# 02-WWVB_Path.net
KiCad netlist of a schematic drawn in Altium Designer
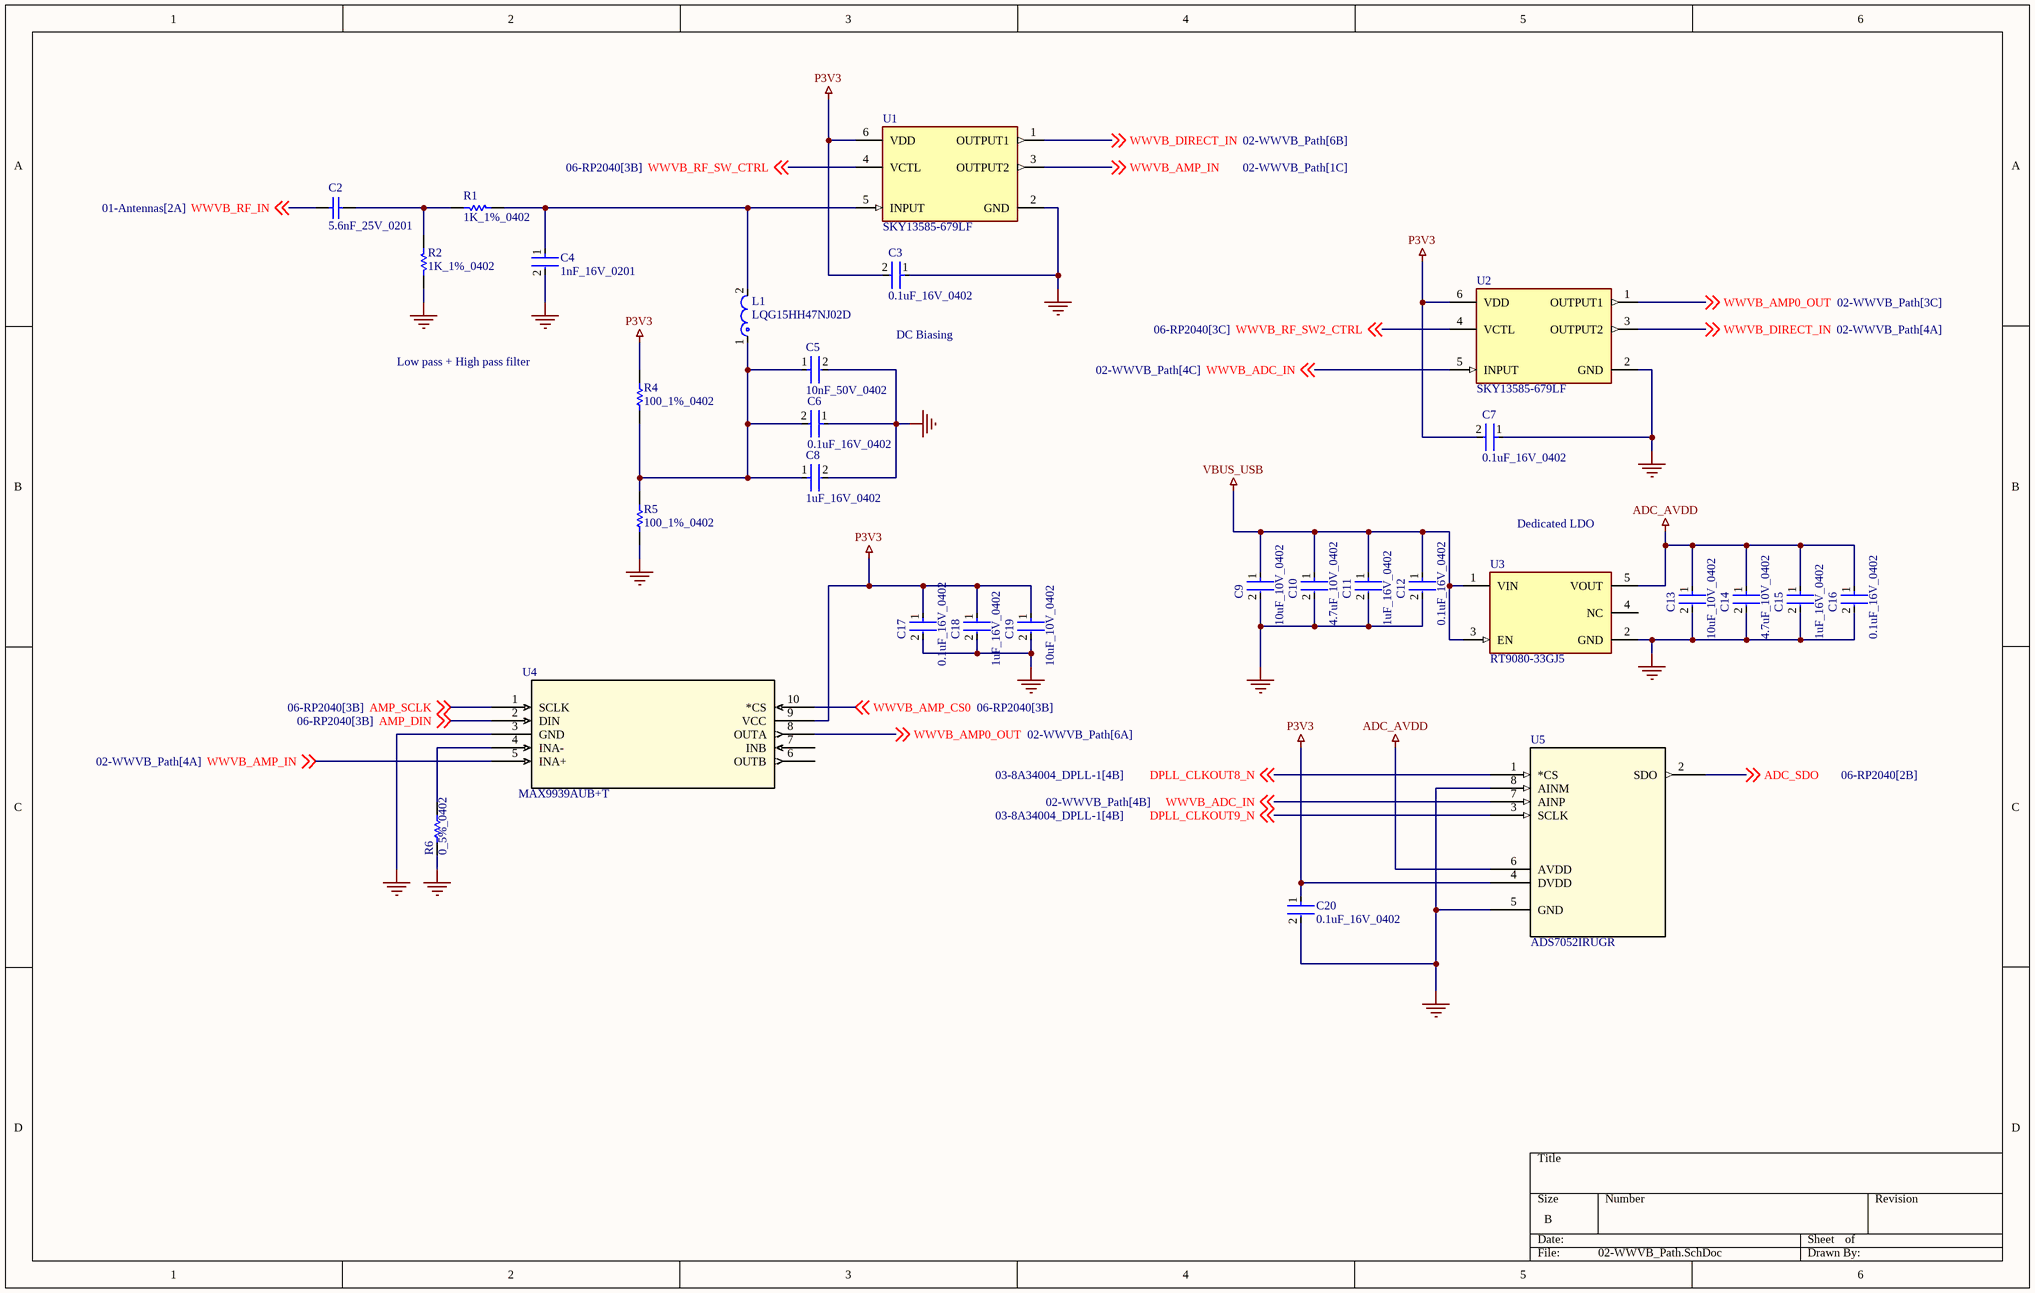
[diagram p0: 02-WWVB_Path.SchDoc]

(export (version "E")
  (design (tool "Eeschema 10.0.6"))
  (components
    (comp (ref "C2")
      (value "5.6nF_25V_0201")
      (footprint "CAPC0603X33X15ML03T05")
      (fields (field (name "PART NUMBER") "MC000322") (field (name "MANUFACTURER") "Multicomp"))
      (libsource (lib "Altium Content Vault") (part "CAP"))
    )
    (comp (ref "C3")
      (value "0.1uF_16V_0402")
      (footprint "FP-C0402-BB-MFG")
      (description "CAP CER 0.1UF 16V 5% X7R 0402")
      (fields
        (field (name "MANUFACTURER") "Kemet")
        (field (name "MANUFACTURER PART NUMBER") "C0402C104J4RACTU")
      )
      (libsource (lib "Altium Content Vault") (part "b4654b650e69147ec39a6b967a45e02"))
    )
    (comp (ref "C4")
      (value "1nF_16V_0201")
      (footprint "FP-0201-L_0_6_0_09-W_0_3-MFG")
      (description "General Purpose Ceramic Capacitor, 0201, 1nF, 10%, X7R, 15%, 16V")
      (fields (field (name "VOLTAGE") "16V") (field (name "TOLERANCE") "10%"))
      (libsource (lib "Altium Content Vault") (part "b4654b650e69147ec39a6b967a45e02"))
    )
    (comp (ref "C5")
      (value "10nF_50V_0402")
      (footprint "FP-CL165-IPC_C")
      (description "Cap Ceramic 10nF 50V X7R ±10% SMD 0402 +125°C Paper T/R")
      (fields (field (name "VOLTAGE") "50V") (field (name "TOLERANCE") "10%"))
      (libsource (lib "Altium Content Vault") (part "b4654b650e69147ec39a6b967a45e02"))
    )
    (comp (ref "C6")
      (value "0.1uF_16V_0402")
      (footprint "FP-C0402-BB-MFG")
      (description "CAP CER 0.1UF 16V 5% X7R 0402")
      (fields
        (field (name "MANUFACTURER") "Kemet")
        (field (name "MANUFACTURER PART NUMBER") "C0402C104J4RACTU")
      )
      (libsource (lib "Altium Content Vault") (part "b4654b650e69147ec39a6b967a45e02"))
    )
    (comp (ref "C7")
      (value "0.1uF_16V_0402")
      (footprint "FP-C0402-BB-MFG")
      (description "CAP CER 0.1UF 16V 5% X7R 0402")
      (fields
        (field (name "MANUFACTURER") "Kemet")
        (field (name "MANUFACTURER PART NUMBER") "C0402C104J4RACTU")
      )
      (libsource (lib "Altium Content Vault") (part "b4654b650e69147ec39a6b967a45e02"))
    )
    (comp (ref "C8")
      (value "1uF_16V_0402")
      (footprint "FP-0402-L_1_0_0_05-W_0_5-IPC_A")
      (description "None")
      (fields (field (name "TOLERANCE") "10%"))
      (libsource (lib "Altium Content Vault") (part "b4654b650e69147ec39a6b967a45e02"))
    )
    (comp (ref "C9")
      (value "10uF_10V_0402")
      (footprint "FP-CL05A106MP5NUNC-MFG")
      (description "CAP CER 10UF 10V X5R 0402")
      (fields
        (field (name "OCTOPART") "https://octopart.com/cl05a106mp5nunc-samsung-22457395")
        (field (name "TOLERANCE") "20%")
      )
      (libsource (lib "Altium Content Vault") (part "b4654b650e69147ec39a6b967a45e02"))
    )
    (comp (ref "C10")
      (value "4.7uF_10V_0402")
      (footprint "FP-C1005-050-0_15-MFG")
      (description "CAP CER 4.7UF 10V X5R 0402")
      (fields (field (name "TOLERANCE") "10%"))
      (libsource (lib "Altium Content Vault") (part "b4654b650e69147ec39a6b967a45e02"))
    )
    (comp (ref "C11")
      (value "1uF_16V_0402")
      (footprint "FP-0402-L_1_0_0_05-W_0_5-IPC_A")
      (description "None")
      (fields (field (name "TOLERANCE") "10%"))
      (libsource (lib "Altium Content Vault") (part "b4654b650e69147ec39a6b967a45e02"))
    )
    (comp (ref "C12")
      (value "0.1uF_16V_0402")
      (footprint "FP-C0402-BB-MFG")
      (description "CAP CER 0.1UF 16V 5% X7R 0402")
      (fields
        (field (name "MANUFACTURER") "Kemet")
        (field (name "MANUFACTURER PART NUMBER") "C0402C104J4RACTU")
      )
      (libsource (lib "Altium Content Vault") (part "b4654b650e69147ec39a6b967a45e02"))
    )
    (comp (ref "C13")
      (value "10uF_10V_0402")
      (footprint "FP-CL05A106MP5NUNC-MFG")
      (description "CAP CER 10UF 10V X5R 0402")
      (fields
        (field (name "OCTOPART") "https://octopart.com/cl05a106mp5nunc-samsung-22457395")
        (field (name "TOLERANCE") "20%")
      )
      (libsource (lib "Altium Content Vault") (part "b4654b650e69147ec39a6b967a45e02"))
    )
    (comp (ref "C14")
      (value "4.7uF_10V_0402")
      (footprint "FP-C1005-050-0_15-MFG")
      (description "CAP CER 4.7UF 10V X5R 0402")
      (fields (field (name "TOLERANCE") "10%"))
      (libsource (lib "Altium Content Vault") (part "b4654b650e69147ec39a6b967a45e02"))
    )
    (comp (ref "C15")
      (value "1uF_16V_0402")
      (footprint "FP-0402-L_1_0_0_05-W_0_5-IPC_A")
      (description "None")
      (fields (field (name "TOLERANCE") "10%"))
      (libsource (lib "Altium Content Vault") (part "b4654b650e69147ec39a6b967a45e02"))
    )
    (comp (ref "C16")
      (value "0.1uF_16V_0402")
      (footprint "FP-C0402-BB-MFG")
      (description "CAP CER 0.1UF 16V 5% X7R 0402")
      (fields
        (field (name "MANUFACTURER") "Kemet")
        (field (name "MANUFACTURER PART NUMBER") "C0402C104J4RACTU")
      )
      (libsource (lib "Altium Content Vault") (part "b4654b650e69147ec39a6b967a45e02"))
    )
    (comp (ref "C17")
      (value "0.1uF_16V_0402")
      (footprint "FP-C0402-BB-MFG")
      (description "CAP CER 0.1UF 16V 5% X7R 0402")
      (fields
        (field (name "MANUFACTURER") "Kemet")
        (field (name "MANUFACTURER PART NUMBER") "C0402C104J4RACTU")
      )
      (libsource (lib "Altium Content Vault") (part "b4654b650e69147ec39a6b967a45e02"))
    )
    (comp (ref "C18")
      (value "1uF_16V_0402")
      (footprint "FP-0402-L_1_0_0_05-W_0_5-IPC_A")
      (description "None")
      (fields (field (name "TOLERANCE") "10%"))
      (libsource (lib "Altium Content Vault") (part "b4654b650e69147ec39a6b967a45e02"))
    )
    (comp (ref "C19")
      (value "10uF_10V_0402")
      (footprint "FP-CL05A106MP5NUNC-MFG")
      (description "CAP CER 10UF 10V X5R 0402")
      (fields
        (field (name "OCTOPART") "https://octopart.com/cl05a106mp5nunc-samsung-22457395")
        (field (name "TOLERANCE") "20%")
      )
      (libsource (lib "Altium Content Vault") (part "b4654b650e69147ec39a6b967a45e02"))
    )
    (comp (ref "C20")
      (value "0.1uF_16V_0402")
      (footprint "FP-C0402-BB-MFG")
      (description "CAP CER 0.1UF 16V 5% X7R 0402")
      (fields
        (field (name "MANUFACTURER") "Kemet")
        (field (name "MANUFACTURER PART NUMBER") "C0402C104J4RACTU")
      )
      (libsource (lib "Altium Content Vault") (part "b4654b650e69147ec39a6b967a45e02"))
    )
    (comp (ref "L1")
      (value "LQG15HH47NJ02D")
      (footprint "FP-LQG15HH_02-IPC_C")
      (description "Multilayer type Inductor for Automotive 47nH ±5% 0.72Ω 300mA 0402")
      (fields (field (name "TOLERANCE") "5%"))
      (libsource (lib "Altium Content Vault") (part "4cc4b267dca4c8e51f7102f422741d8"))
    )
    (comp (ref "R1")
      (value "1K_1%_0402")
      (footprint "RESC1005X40X25NL05T05")
      (fields (field (name "MANUFACTURER") "Vishay Dale") (field (name "PART NUMBER") "CRCW04021K00FKTD"))
      (libsource (lib "Altium Content Vault") (part "RES"))
    )
    (comp (ref "R2")
      (value "1K_1%_0402")
      (footprint "RESC1005X40X25NL05T05")
      (fields (field (name "MANUFACTURER") "Vishay Dale") (field (name "PART NUMBER") "CRCW04021K00FKTD"))
      (libsource (lib "Altium Content Vault") (part "RES"))
    )
    (comp (ref "R4")
      (value "100_1%_0402")
      (footprint "RESC1005X40X25ML05T10")
      (fields (field (name "PART NUMBER") "ERJ-U02F1000X") (field (name "MANUFACTURER") "Panasonic"))
      (libsource (lib "Altium Content Vault") (part "RES"))
    )
    (comp (ref "R5")
      (value "100_1%_0402")
      (footprint "RESC1005X40X25ML05T10")
      (fields (field (name "PART NUMBER") "ERJ-U02F1000X") (field (name "MANUFACTURER") "Panasonic"))
      (libsource (lib "Altium Content Vault") (part "RES"))
    )
    (comp (ref "R6")
      (value "0_5%_0402")
      (footprint "RESC1005X40X25NL05T10")
      (fields (field (name "MANUFACTURER") "Panasonic") (field (name "PART NUMBER") "ERJ-U020R00X"))
      (libsource (lib "Altium Content Vault") (part "RES"))
    )
    (comp (ref "U1")
      (value "SKY13585-679LF")
      (footprint "FP-SKY13585-679LF-MFG")
      (description "IC RF SWITCH SPDT 6GHZ 6MLPD")
      (libsource (lib "Altium Content Vault") (part "e67e48af39ab44f3294fce00d3e4f12"))
    )
    (comp (ref "U2")
      (value "SKY13585-679LF")
      (footprint "FP-SKY13585-679LF-MFG")
      (description "IC RF SWITCH SPDT 6GHZ 6MLPD")
      (libsource (lib "Altium Content Vault") (part "e67e48af39ab44f3294fce00d3e4f12"))
    )
    (comp (ref "U3")
      (value "RT9080-33GJ5")
      (footprint "FP-RT9080-33GJ5-IPC_C")
      (description "IC REG LIN 3.3V 600MA TSOT23-5")
      (libsource (lib "Altium Content Vault") (part "f644620f29190e8f0733f9129712cb2"))
    )
    (comp (ref "U4")
      (value "MAX9939AUB+T")
      (footprint "21-0061L_MXM")
      (description "No Description Available")
      (fields (field (name "COPYRIGHT") "Copyright (C) 2023 Ultra Librarian. All rights reserved."))
      (libsource (lib "MAX9939AUB&plus_T") (part "MAX9939AUB+T"))
    )
    (comp (ref "U5")
      (value "ADS7052IRUGR")
      (footprint "RUG8_TEX")
      (description "No Description Available")
      (libsource (lib "ADS7052IRUGR") (part "ADS7052IRUGR"))
    )
  )
  (nets
    (net (code "1") (name "ADC_AVDD") (class "Default")
      (node (ref "C13") (pin "1") (pinfunction "1_1") (pintype "passive"))
      (node (ref "C14") (pin "1") (pinfunction "1_1") (pintype "passive"))
      (node (ref "C15") (pin "1") (pinfunction "1_1") (pintype "passive"))
      (node (ref "C16") (pin "1") (pinfunction "1_1") (pintype "passive"))
      (node (ref "U3") (pin "5") (pinfunction "VOUT_5") (pintype "passive"))
      (node (ref "U5") (pin "6") (pinfunction "AVDD_6") (pintype "power_in"))
    )
    (net (code "2") (name "ADC_SDO") (class "Default")
      (node (ref "U5") (pin "2") (pinfunction "SDO_2") (pintype "output"))
    )
    (net (code "3") (name "AMP_DIN") (class "Default")
      (node (ref "U4") (pin "2") (pinfunction "DIN_2") (pintype "input"))
    )
    (net (code "4") (name "AMP_SCLK") (class "Default")
      (node (ref "U4") (pin "1") (pinfunction "SCLK_1") (pintype "input"))
    )
    (net (code "5") (name "DPLL_CLKOUT8_N") (class "Default")
      (node (ref "U5") (pin "1") (pinfunction "*CS_1") (pintype "input"))
    )
    (net (code "6") (name "DPLL_CLKOUT9_N") (class "Default")
      (node (ref "U5") (pin "3") (pinfunction "SCLK_3") (pintype "input"))
    )
    (net (code "7") (name "GND") (class "Default")
      (node (ref "C10") (pin "2") (pinfunction "2_2") (pintype "passive"))
      (node (ref "C11") (pin "2") (pinfunction "2_2") (pintype "passive"))
      (node (ref "C12") (pin "2") (pinfunction "2_2") (pintype "passive"))
      (node (ref "C13") (pin "2") (pinfunction "2_2") (pintype "passive"))
      (node (ref "C14") (pin "2") (pinfunction "2_2") (pintype "passive"))
      (node (ref "C15") (pin "2") (pinfunction "2_2") (pintype "passive"))
      (node (ref "C16") (pin "2") (pinfunction "2_2") (pintype "passive"))
      (node (ref "C17") (pin "2") (pinfunction "2_2") (pintype "passive"))
      (node (ref "C18") (pin "2") (pinfunction "2_2") (pintype "passive"))
      (node (ref "C19") (pin "2") (pinfunction "2_2") (pintype "passive"))
      (node (ref "C20") (pin "2") (pinfunction "2_2") (pintype "passive"))
      (node (ref "C3") (pin "1") (pinfunction "1_1") (pintype "passive"))
      (node (ref "C4") (pin "2") (pinfunction "2_2") (pintype "passive"))
      (node (ref "C5") (pin "2") (pinfunction "2_2") (pintype "passive"))
      (node (ref "C6") (pin "1") (pinfunction "1_1") (pintype "passive"))
      (node (ref "C7") (pin "1") (pinfunction "1_1") (pintype "passive"))
      (node (ref "C8") (pin "2") (pinfunction "2_2") (pintype "passive"))
      (node (ref "C9") (pin "2") (pinfunction "2_2") (pintype "passive"))
      (node (ref "R2") (pin "1") (pinfunction "1_1") (pintype "passive"))
      (node (ref "R5") (pin "1") (pinfunction "1_1") (pintype "passive"))
      (node (ref "R6") (pin "1") (pinfunction "1_1") (pintype "passive"))
      (node (ref "U1") (pin "2") (pinfunction "GND_2") (pintype "power_in"))
      (node (ref "U2") (pin "2") (pinfunction "GND_2") (pintype "power_in"))
      (node (ref "U3") (pin "2") (pinfunction "GND_2") (pintype "power_in"))
      (node (ref "U4") (pin "3") (pinfunction "GND_3") (pintype "power_in"))
      (node (ref "U5") (pin "5") (pinfunction "GND_5") (pintype "power_in"))
      (node (ref "U5") (pin "8") (pinfunction "AINM_8") (pintype "input"))
    )
    (net (code "8") (name "Net-(C2-Pad2)") (class "Default")
      (node (ref "C2") (pin "2") (pinfunction "2_2") (pintype "passive"))
      (node (ref "R1") (pin "2") (pinfunction "2_2") (pintype "passive"))
      (node (ref "R2") (pin "2") (pinfunction "2_2") (pintype "passive"))
    )
    (net (code "9") (name "Net-(C5-Pad1)") (class "Default")
      (node (ref "C5") (pin "1") (pinfunction "1_1") (pintype "passive"))
      (node (ref "C6") (pin "2") (pinfunction "2_2") (pintype "passive"))
      (node (ref "C8") (pin "1") (pinfunction "1_1") (pintype "passive"))
      (node (ref "L1") (pin "1") (pinfunction "1_1") (pintype "passive"))
      (node (ref "R4") (pin "1") (pinfunction "1_1") (pintype "passive"))
      (node (ref "R5") (pin "2") (pinfunction "2_2") (pintype "passive"))
    )
    (net (code "10") (name "Net-(U1-INPUT)") (class "Default")
      (node (ref "C4") (pin "1") (pinfunction "1_1") (pintype "passive"))
      (node (ref "L1") (pin "2") (pinfunction "2_2") (pintype "passive"))
      (node (ref "R1") (pin "1") (pinfunction "1_1") (pintype "passive"))
      (node (ref "U1") (pin "5") (pinfunction "INPUT_5") (pintype "input"))
    )
    (net (code "11") (name "Net-(U4-INA-)") (class "Default")
      (node (ref "R6") (pin "2") (pinfunction "2_2") (pintype "passive"))
      (node (ref "U4") (pin "4") (pinfunction "INA-_4") (pintype "input"))
    )
    (net (code "12") (name "P3V3") (class "Default")
      (node (ref "C17") (pin "1") (pinfunction "1_1") (pintype "passive"))
      (node (ref "C18") (pin "1") (pinfunction "1_1") (pintype "passive"))
      (node (ref "C19") (pin "1") (pinfunction "1_1") (pintype "passive"))
      (node (ref "C20") (pin "1") (pinfunction "1_1") (pintype "passive"))
      (node (ref "C3") (pin "2") (pinfunction "2_2") (pintype "passive"))
      (node (ref "C7") (pin "2") (pinfunction "2_2") (pintype "passive"))
      (node (ref "R4") (pin "2") (pinfunction "2_2") (pintype "passive"))
      (node (ref "U1") (pin "6") (pinfunction "VDD_6") (pintype "power_in"))
      (node (ref "U2") (pin "6") (pinfunction "VDD_6") (pintype "power_in"))
      (node (ref "U4") (pin "9") (pinfunction "VCC_9") (pintype "power_in"))
      (node (ref "U5") (pin "4") (pinfunction "DVDD_4") (pintype "power_in"))
    )
    (net (code "13") (name "VBUS_USB") (class "Default")
      (node (ref "C10") (pin "1") (pinfunction "1_1") (pintype "passive"))
      (node (ref "C11") (pin "1") (pinfunction "1_1") (pintype "passive"))
      (node (ref "C12") (pin "1") (pinfunction "1_1") (pintype "passive"))
      (node (ref "C9") (pin "1") (pinfunction "1_1") (pintype "passive"))
      (node (ref "U3") (pin "1") (pinfunction "VIN_1") (pintype "power_in"))
      (node (ref "U3") (pin "3") (pinfunction "EN_3") (pintype "input"))
    )
    (net (code "14") (name "WWVB_ADC_IN") (class "Default")
      (node (ref "U2") (pin "5") (pinfunction "INPUT_5") (pintype "input"))
      (node (ref "U5") (pin "7") (pinfunction "AINP_7") (pintype "input"))
    )
    (net (code "15") (name "WWVB_AMP0_OUT") (class "Default")
      (node (ref "U2") (pin "1") (pinfunction "OUTPUT1_1") (pintype "output"))
      (node (ref "U4") (pin "8") (pinfunction "OUTA_8") (pintype "output"))
    )
    (net (code "16") (name "WWVB_AMP_CS0") (class "Default")
      (node (ref "U4") (pin "10") (pinfunction "*CS_10") (pintype "input"))
    )
    (net (code "17") (name "WWVB_AMP_IN") (class "Default")
      (node (ref "U1") (pin "3") (pinfunction "OUTPUT2_3") (pintype "output"))
      (node (ref "U4") (pin "5") (pinfunction "INA+_5") (pintype "input"))
    )
    (net (code "18") (name "WWVB_DIRECT_IN") (class "Default")
      (node (ref "U1") (pin "1") (pinfunction "OUTPUT1_1") (pintype "output"))
      (node (ref "U2") (pin "3") (pinfunction "OUTPUT2_3") (pintype "output"))
    )
    (net (code "19") (name "WWVB_RF_IN") (class "Default")
      (node (ref "C2") (pin "1") (pinfunction "1_1") (pintype "passive"))
    )
    (net (code "20") (name "WWVB_RF_SW2_CTRL") (class "Default")
      (node (ref "U2") (pin "4") (pinfunction "VCTL_4") (pintype "power_in"))
    )
    (net (code "21") (name "WWVB_RF_SW_CTRL") (class "Default")
      (node (ref "U1") (pin "4") (pinfunction "VCTL_4") (pintype "power_in"))
    )
    (net (code "22") (name "unconnected-(U3-NC-Pad4)") (class "Default")
      (node (ref "U3") (pin "4") (pinfunction "NC_4") (pintype "passive"))
    )
    (net (code "23") (name "unconnected-(U4-INB-Pad7)") (class "Default")
      (node (ref "U4") (pin "7") (pinfunction "INB_7") (pintype "input"))
    )
    (net (code "24") (name "unconnected-(U4-OUTB-Pad6)") (class "Default")
      (node (ref "U4") (pin "6") (pinfunction "OUTB_6") (pintype "output"))
    )
  )
)
